# Trex.net
KiCad netlist of a schematic drawn in Altium Designer
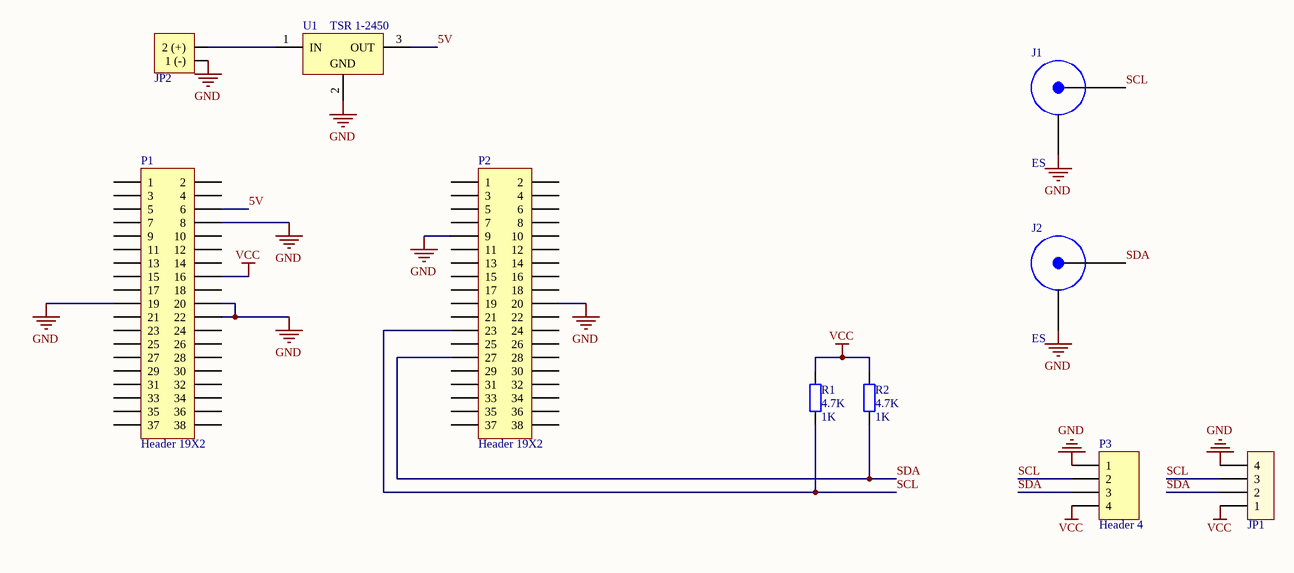
[diagram p0: Trex.SchDoc]

(export (version "E")
  (design (tool "Eeschema 10.0.6"))
  (components
    (comp (ref "J1") (value "ES") (footprint "BNC") (libsource (lib "Gamel_Trophy_v4re1") (part "BNC")))
    (comp (ref "J2") (value "ES") (footprint "BNC") (libsource (lib "Gamel_Trophy_v4re1") (part "BNC")))
    (comp (ref "JP1")
      (value "Connecteur Autocom 4pts")
      (footprint "Autocom HE14 - 4 - Coudé")
      (description "connecteur autocom HE14 4 pts")
      (fields
        (field (name "MANUFACTURER") "TE CONNECTIVITY / AMP")
        (field (name "MANUFACTURER PART NUMBER") "281698-4")
      )
      (libsource (lib "GEII") (part "Connecteur Autocom 4 pts"))
    )
    (comp (ref "JP2")
      (value "Connecteur alim 2 pts")
      (footprint "entrelec 2 PTS")
      (libsource (lib "Gamel_Trophy_v4re1") (part "Connecteur alim 2 pts"))
    )
    (comp (ref "P1")
      (value "Header 19X2")
      (footprint "HDR2X19")
      (description "Header, 19-Pin, Dual row")
      (fields (field (name "PUBLISHER") "Altium Limited"))
      (libsource (lib "Miscellaneous Connectors") (part "Header 19X2"))
    )
    (comp (ref "P2")
      (value "Header 19X2")
      (footprint "HDR2X19")
      (description "Header, 19-Pin, Dual row")
      (fields (field (name "PUBLISHER") "Altium Limited"))
      (libsource (lib "Miscellaneous Connectors") (part "Header 19X2"))
    )
    (comp (ref "P3")
      (value "Header 4")
      (footprint "HDR1X4")
      (description "Header, 4-Pin")
      (fields (field (name "PUBLISHER") "Altium Limited"))
      (libsource (lib "Miscellaneous Connectors") (part "Header 4"))
    )
    (comp (ref "R1")
      (value "4.7K")
      (footprint "AXIAL-0.4")
      (description "Resistor")
      (fields (field (name "ALTIUM_VALUE") "1K") (field (name "PUBLISHER") "Altium Limited"))
      (libsource (lib "Miscellaneous Devices") (part "Res2"))
    )
    (comp (ref "R2")
      (value "4.7K")
      (footprint "AXIAL-0.4")
      (description "Resistor")
      (fields (field (name "ALTIUM_VALUE") "1K") (field (name "PUBLISHER") "Altium Limited"))
      (libsource (lib "Miscellaneous Devices") (part "Res2"))
    )
    (comp (ref "U1")
      (value "TSR 1-2450")
      (footprint "TSR-1")
      (description "DC/DC Converters  TSR-1 Series, 1 A")
      (fields (field (name "MANUFACTURER") "TRACOPOWER") (field (name "PUBLISHER") "H.Angelis"))
      (libsource (lib "GEII") (part "TSR 1-2450"))
    )
  )
  (nets
    (net (code "1") (name "/5V") (class "Default")
      (node (ref "P1") (pin "6") (pinfunction "6_6") (pintype "passive"))
      (node (ref "U1") (pin "3") (pinfunction "OUT_3") (pintype "passive"))
    )
    (net (code "2") (name "/SCL") (class "Default")
      (node (ref "J1") (pin "1") (pinfunction "SIGNAL_1") (pintype "passive"))
      (node (ref "JP1") (pin "3") (pinfunction "3_3") (pintype "passive"))
      (node (ref "P2") (pin "23") (pinfunction "23_23") (pintype "passive"))
      (node (ref "P3") (pin "2") (pinfunction "2_2") (pintype "passive"))
      (node (ref "R1") (pin "1") (pinfunction "1_1") (pintype "passive"))
    )
    (net (code "3") (name "/SDA") (class "Default")
      (node (ref "J2") (pin "1") (pinfunction "SIGNAL_1") (pintype "passive"))
      (node (ref "JP1") (pin "2") (pinfunction "2_2") (pintype "passive"))
      (node (ref "P2") (pin "27") (pinfunction "27_27") (pintype "passive"))
      (node (ref "P3") (pin "3") (pinfunction "3_3") (pintype "passive"))
      (node (ref "R2") (pin "1") (pinfunction "1_1") (pintype "passive"))
    )
    (net (code "4") (name "GND") (class "Default")
      (node (ref "J1") (pin "2") (pinfunction "GND_2") (pintype "passive"))
      (node (ref "J2") (pin "2") (pinfunction "GND_2") (pintype "passive"))
      (node (ref "JP1") (pin "4") (pinfunction "4_4") (pintype "passive"))
      (node (ref "JP2") (pin "1") (pinfunction "1_(-)_1") (pintype "passive"))
      (node (ref "P1") (pin "19") (pinfunction "19_19") (pintype "passive"))
      (node (ref "P1") (pin "20") (pinfunction "20_20") (pintype "passive"))
      (node (ref "P1") (pin "22") (pinfunction "22_22") (pintype "passive"))
      (node (ref "P1") (pin "8") (pinfunction "8_8") (pintype "passive"))
      (node (ref "P2") (pin "20") (pinfunction "20_20") (pintype "passive"))
      (node (ref "P2") (pin "9") (pinfunction "9_9") (pintype "passive"))
      (node (ref "P3") (pin "1") (pinfunction "1_1") (pintype "passive"))
      (node (ref "U1") (pin "2") (pinfunction "GND_2") (pintype "passive"))
    )
    (net (code "5") (name "Net-(JP2-2_(+))") (class "Default")
      (node (ref "JP2") (pin "2") (pinfunction "2_(+)_2") (pintype "passive"))
      (node (ref "U1") (pin "1") (pinfunction "IN_1") (pintype "passive"))
    )
    (net (code "6") (name "VCC") (class "Default")
      (node (ref "JP1") (pin "1") (pinfunction "1_1") (pintype "passive"))
      (node (ref "P1") (pin "16") (pinfunction "16_16") (pintype "passive"))
      (node (ref "P3") (pin "4") (pinfunction "4_4") (pintype "passive"))
      (node (ref "R1") (pin "2") (pinfunction "2_2") (pintype "passive"))
      (node (ref "R2") (pin "2") (pinfunction "2_2") (pintype "passive"))
    )
    (net (code "7") (name "unconnected-(P1-Pad1)") (class "Default")
      (node (ref "P1") (pin "1") (pinfunction "1_1") (pintype "passive"))
    )
    (net (code "8") (name "unconnected-(P1-Pad2)") (class "Default")
      (node (ref "P1") (pin "2") (pinfunction "2_2") (pintype "passive"))
    )
    (net (code "9") (name "unconnected-(P1-Pad3)") (class "Default")
      (node (ref "P1") (pin "3") (pinfunction "3_3") (pintype "passive"))
    )
    (net (code "10") (name "unconnected-(P1-Pad4)") (class "Default")
      (node (ref "P1") (pin "4") (pinfunction "4_4") (pintype "passive"))
    )
    (net (code "11") (name "unconnected-(P1-Pad5)") (class "Default")
      (node (ref "P1") (pin "5") (pinfunction "5_5") (pintype "passive"))
    )
    (net (code "12") (name "unconnected-(P1-Pad7)") (class "Default")
      (node (ref "P1") (pin "7") (pinfunction "7_7") (pintype "passive"))
    )
    (net (code "13") (name "unconnected-(P1-Pad9)") (class "Default")
      (node (ref "P1") (pin "9") (pinfunction "9_9") (pintype "passive"))
    )
    (net (code "14") (name "unconnected-(P1-Pad10)") (class "Default")
      (node (ref "P1") (pin "10") (pinfunction "10_10") (pintype "passive"))
    )
    (net (code "15") (name "unconnected-(P1-Pad11)") (class "Default")
      (node (ref "P1") (pin "11") (pinfunction "11_11") (pintype "passive"))
    )
    (net (code "16") (name "unconnected-(P1-Pad12)") (class "Default")
      (node (ref "P1") (pin "12") (pinfunction "12_12") (pintype "passive"))
    )
    (net (code "17") (name "unconnected-(P1-Pad13)") (class "Default")
      (node (ref "P1") (pin "13") (pinfunction "13_13") (pintype "passive"))
    )
    (net (code "18") (name "unconnected-(P1-Pad14)") (class "Default")
      (node (ref "P1") (pin "14") (pinfunction "14_14") (pintype "passive"))
    )
    (net (code "19") (name "unconnected-(P1-Pad15)") (class "Default")
      (node (ref "P1") (pin "15") (pinfunction "15_15") (pintype "passive"))
    )
    (net (code "20") (name "unconnected-(P1-Pad17)") (class "Default")
      (node (ref "P1") (pin "17") (pinfunction "17_17") (pintype "passive"))
    )
    (net (code "21") (name "unconnected-(P1-Pad18)") (class "Default")
      (node (ref "P1") (pin "18") (pinfunction "18_18") (pintype "passive"))
    )
    (net (code "22") (name "unconnected-(P1-Pad21)") (class "Default")
      (node (ref "P1") (pin "21") (pinfunction "21_21") (pintype "passive"))
    )
    (net (code "23") (name "unconnected-(P1-Pad23)") (class "Default")
      (node (ref "P1") (pin "23") (pinfunction "23_23") (pintype "passive"))
    )
    (net (code "24") (name "unconnected-(P1-Pad24)") (class "Default")
      (node (ref "P1") (pin "24") (pinfunction "24_24") (pintype "passive"))
    )
    (net (code "25") (name "unconnected-(P1-Pad25)") (class "Default")
      (node (ref "P1") (pin "25") (pinfunction "25_25") (pintype "passive"))
    )
    (net (code "26") (name "unconnected-(P1-Pad26)") (class "Default")
      (node (ref "P1") (pin "26") (pinfunction "26_26") (pintype "passive"))
    )
    (net (code "27") (name "unconnected-(P1-Pad27)") (class "Default")
      (node (ref "P1") (pin "27") (pinfunction "27_27") (pintype "passive"))
    )
    (net (code "28") (name "unconnected-(P1-Pad28)") (class "Default")
      (node (ref "P1") (pin "28") (pinfunction "28_28") (pintype "passive"))
    )
    (net (code "29") (name "unconnected-(P1-Pad29)") (class "Default")
      (node (ref "P1") (pin "29") (pinfunction "29_29") (pintype "passive"))
    )
    (net (code "30") (name "unconnected-(P1-Pad30)") (class "Default")
      (node (ref "P1") (pin "30") (pinfunction "30_30") (pintype "passive"))
    )
    (net (code "31") (name "unconnected-(P1-Pad31)") (class "Default")
      (node (ref "P1") (pin "31") (pinfunction "31_31") (pintype "passive"))
    )
    (net (code "32") (name "unconnected-(P1-Pad32)") (class "Default")
      (node (ref "P1") (pin "32") (pinfunction "32_32") (pintype "passive"))
    )
    (net (code "33") (name "unconnected-(P1-Pad33)") (class "Default")
      (node (ref "P1") (pin "33") (pinfunction "33_33") (pintype "passive"))
    )
    (net (code "34") (name "unconnected-(P1-Pad34)") (class "Default")
      (node (ref "P1") (pin "34") (pinfunction "34_34") (pintype "passive"))
    )
    (net (code "35") (name "unconnected-(P1-Pad35)") (class "Default")
      (node (ref "P1") (pin "35") (pinfunction "35_35") (pintype "passive"))
    )
    (net (code "36") (name "unconnected-(P1-Pad36)") (class "Default")
      (node (ref "P1") (pin "36") (pinfunction "36_36") (pintype "passive"))
    )
    (net (code "37") (name "unconnected-(P1-Pad37)") (class "Default")
      (node (ref "P1") (pin "37") (pinfunction "37_37") (pintype "passive"))
    )
    (net (code "38") (name "unconnected-(P1-Pad38)") (class "Default")
      (node (ref "P1") (pin "38") (pinfunction "38_38") (pintype "passive"))
    )
    (net (code "39") (name "unconnected-(P2-Pad1)") (class "Default")
      (node (ref "P2") (pin "1") (pinfunction "1_1") (pintype "passive"))
    )
    (net (code "40") (name "unconnected-(P2-Pad2)") (class "Default")
      (node (ref "P2") (pin "2") (pinfunction "2_2") (pintype "passive"))
    )
    (net (code "41") (name "unconnected-(P2-Pad3)") (class "Default")
      (node (ref "P2") (pin "3") (pinfunction "3_3") (pintype "passive"))
    )
    (net (code "42") (name "unconnected-(P2-Pad4)") (class "Default")
      (node (ref "P2") (pin "4") (pinfunction "4_4") (pintype "passive"))
    )
    (net (code "43") (name "unconnected-(P2-Pad5)") (class "Default")
      (node (ref "P2") (pin "5") (pinfunction "5_5") (pintype "passive"))
    )
    (net (code "44") (name "unconnected-(P2-Pad6)") (class "Default")
      (node (ref "P2") (pin "6") (pinfunction "6_6") (pintype "passive"))
    )
    (net (code "45") (name "unconnected-(P2-Pad7)") (class "Default")
      (node (ref "P2") (pin "7") (pinfunction "7_7") (pintype "passive"))
    )
    (net (code "46") (name "unconnected-(P2-Pad8)") (class "Default")
      (node (ref "P2") (pin "8") (pinfunction "8_8") (pintype "passive"))
    )
    (net (code "47") (name "unconnected-(P2-Pad10)") (class "Default")
      (node (ref "P2") (pin "10") (pinfunction "10_10") (pintype "passive"))
    )
    (net (code "48") (name "unconnected-(P2-Pad11)") (class "Default")
      (node (ref "P2") (pin "11") (pinfunction "11_11") (pintype "passive"))
    )
    (net (code "49") (name "unconnected-(P2-Pad12)") (class "Default")
      (node (ref "P2") (pin "12") (pinfunction "12_12") (pintype "passive"))
    )
    (net (code "50") (name "unconnected-(P2-Pad13)") (class "Default")
      (node (ref "P2") (pin "13") (pinfunction "13_13") (pintype "passive"))
    )
    (net (code "51") (name "unconnected-(P2-Pad14)") (class "Default")
      (node (ref "P2") (pin "14") (pinfunction "14_14") (pintype "passive"))
    )
    (net (code "52") (name "unconnected-(P2-Pad15)") (class "Default")
      (node (ref "P2") (pin "15") (pinfunction "15_15") (pintype "passive"))
    )
    (net (code "53") (name "unconnected-(P2-Pad16)") (class "Default")
      (node (ref "P2") (pin "16") (pinfunction "16_16") (pintype "passive"))
    )
    (net (code "54") (name "unconnected-(P2-Pad17)") (class "Default")
      (node (ref "P2") (pin "17") (pinfunction "17_17") (pintype "passive"))
    )
    (net (code "55") (name "unconnected-(P2-Pad18)") (class "Default")
      (node (ref "P2") (pin "18") (pinfunction "18_18") (pintype "passive"))
    )
    (net (code "56") (name "unconnected-(P2-Pad19)") (class "Default")
      (node (ref "P2") (pin "19") (pinfunction "19_19") (pintype "passive"))
    )
    (net (code "57") (name "unconnected-(P2-Pad21)") (class "Default")
      (node (ref "P2") (pin "21") (pinfunction "21_21") (pintype "passive"))
    )
    (net (code "58") (name "unconnected-(P2-Pad22)") (class "Default")
      (node (ref "P2") (pin "22") (pinfunction "22_22") (pintype "passive"))
    )
    (net (code "59") (name "unconnected-(P2-Pad24)") (class "Default")
      (node (ref "P2") (pin "24") (pinfunction "24_24") (pintype "passive"))
    )
    (net (code "60") (name "unconnected-(P2-Pad25)") (class "Default")
      (node (ref "P2") (pin "25") (pinfunction "25_25") (pintype "passive"))
    )
    (net (code "61") (name "unconnected-(P2-Pad26)") (class "Default")
      (node (ref "P2") (pin "26") (pinfunction "26_26") (pintype "passive"))
    )
    (net (code "62") (name "unconnected-(P2-Pad28)") (class "Default")
      (node (ref "P2") (pin "28") (pinfunction "28_28") (pintype "passive"))
    )
    (net (code "63") (name "unconnected-(P2-Pad29)") (class "Default")
      (node (ref "P2") (pin "29") (pinfunction "29_29") (pintype "passive"))
    )
    (net (code "64") (name "unconnected-(P2-Pad30)") (class "Default")
      (node (ref "P2") (pin "30") (pinfunction "30_30") (pintype "passive"))
    )
    (net (code "65") (name "unconnected-(P2-Pad31)") (class "Default")
      (node (ref "P2") (pin "31") (pinfunction "31_31") (pintype "passive"))
    )
    (net (code "66") (name "unconnected-(P2-Pad32)") (class "Default")
      (node (ref "P2") (pin "32") (pinfunction "32_32") (pintype "passive"))
    )
    (net (code "67") (name "unconnected-(P2-Pad33)") (class "Default")
      (node (ref "P2") (pin "33") (pinfunction "33_33") (pintype "passive"))
    )
    (net (code "68") (name "unconnected-(P2-Pad34)") (class "Default")
      (node (ref "P2") (pin "34") (pinfunction "34_34") (pintype "passive"))
    )
    (net (code "69") (name "unconnected-(P2-Pad35)") (class "Default")
      (node (ref "P2") (pin "35") (pinfunction "35_35") (pintype "passive"))
    )
    (net (code "70") (name "unconnected-(P2-Pad36)") (class "Default")
      (node (ref "P2") (pin "36") (pinfunction "36_36") (pintype "passive"))
    )
    (net (code "71") (name "unconnected-(P2-Pad37)") (class "Default")
      (node (ref "P2") (pin "37") (pinfunction "37_37") (pintype "passive"))
    )
    (net (code "72") (name "unconnected-(P2-Pad38)") (class "Default")
      (node (ref "P2") (pin "38") (pinfunction "38_38") (pintype "passive"))
    )
  )
)
